# PL_DDR_Power.net
KiCad netlist of a schematic drawn in Altium Designer
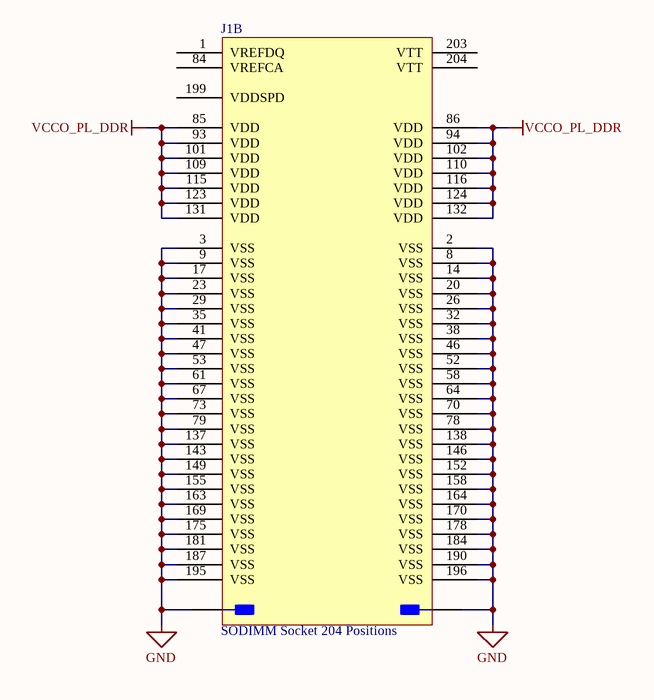
[diagram p0: PL_DDR_Power.SchDoc]

(export (version "E")
  (design (tool "Eeschema 10.0.6"))
  (components
    (comp (ref "J1")
      (value "SODIMM Socket 204 Positions")
      (footprint "TE_DDR3_SODIMM_RA_Socket")
      (description "Connector SODIMM Socket 204 Positions, Right Angle, DDR3/DDR3L +1.5V +1.35V")
      (libsource (lib "SpaceVNX") (part "2-2013310-1"))
    )
  )
  (nets
    (net (code "1") (name "GND") (class "Default")
      (node (ref "J1") (pin "137") (pinfunction "VSS_137") (pintype "passive"))
      (node (ref "J1") (pin "138") (pinfunction "VSS_138") (pintype "passive"))
      (node (ref "J1") (pin "14") (pinfunction "VSS_14") (pintype "passive"))
      (node (ref "J1") (pin "143") (pinfunction "VSS_143") (pintype "passive"))
      (node (ref "J1") (pin "146") (pinfunction "VSS_146") (pintype "passive"))
      (node (ref "J1") (pin "149") (pinfunction "VSS_149") (pintype "passive"))
      (node (ref "J1") (pin "152") (pinfunction "VSS_152") (pintype "passive"))
      (node (ref "J1") (pin "155") (pinfunction "VSS_155") (pintype "passive"))
      (node (ref "J1") (pin "158") (pinfunction "VSS_158") (pintype "passive"))
      (node (ref "J1") (pin "163") (pinfunction "VSS_163") (pintype "passive"))
      (node (ref "J1") (pin "164") (pinfunction "VSS_164") (pintype "passive"))
      (node (ref "J1") (pin "169") (pinfunction "VSS_169") (pintype "passive"))
      (node (ref "J1") (pin "17") (pinfunction "VSS_17") (pintype "passive"))
      (node (ref "J1") (pin "170") (pinfunction "VSS_170") (pintype "passive"))
      (node (ref "J1") (pin "175") (pinfunction "VSS_175") (pintype "passive"))
      (node (ref "J1") (pin "178") (pinfunction "VSS_178") (pintype "passive"))
      (node (ref "J1") (pin "181") (pinfunction "VSS_181") (pintype "passive"))
      (node (ref "J1") (pin "184") (pinfunction "VSS_184") (pintype "passive"))
      (node (ref "J1") (pin "187") (pinfunction "VSS_187") (pintype "passive"))
      (node (ref "J1") (pin "190") (pinfunction "VSS_190") (pintype "passive"))
      (node (ref "J1") (pin "195") (pinfunction "VSS_195") (pintype "passive"))
      (node (ref "J1") (pin "196") (pinfunction "VSS_196") (pintype "passive"))
      (node (ref "J1") (pin "2") (pinfunction "VSS_2") (pintype "passive"))
      (node (ref "J1") (pin "20") (pinfunction "VSS_20") (pintype "passive"))
      (node (ref "J1") (pin "205") (pinfunction "GND_205") (pintype "passive"))
      (node (ref "J1") (pin "206") (pinfunction "GND_206") (pintype "passive"))
      (node (ref "J1") (pin "23") (pinfunction "VSS_23") (pintype "passive"))
      (node (ref "J1") (pin "26") (pinfunction "VSS_26") (pintype "passive"))
      (node (ref "J1") (pin "29") (pinfunction "VSS_29") (pintype "passive"))
      (node (ref "J1") (pin "3") (pinfunction "VSS_3") (pintype "passive"))
      (node (ref "J1") (pin "32") (pinfunction "VSS_32") (pintype "passive"))
      (node (ref "J1") (pin "35") (pinfunction "VSS_35") (pintype "passive"))
      (node (ref "J1") (pin "38") (pinfunction "VSS_38") (pintype "passive"))
      (node (ref "J1") (pin "41") (pinfunction "VSS_41") (pintype "passive"))
      (node (ref "J1") (pin "46") (pinfunction "VSS_46") (pintype "passive"))
      (node (ref "J1") (pin "47") (pinfunction "VSS_47") (pintype "passive"))
      (node (ref "J1") (pin "52") (pinfunction "VSS_52") (pintype "passive"))
      (node (ref "J1") (pin "53") (pinfunction "VSS_53") (pintype "passive"))
      (node (ref "J1") (pin "58") (pinfunction "VSS_58") (pintype "passive"))
      (node (ref "J1") (pin "61") (pinfunction "VSS_61") (pintype "passive"))
      (node (ref "J1") (pin "64") (pinfunction "VSS_64") (pintype "passive"))
      (node (ref "J1") (pin "67") (pinfunction "VSS_67") (pintype "passive"))
      (node (ref "J1") (pin "70") (pinfunction "VSS_70") (pintype "passive"))
      (node (ref "J1") (pin "73") (pinfunction "VSS_73") (pintype "passive"))
      (node (ref "J1") (pin "78") (pinfunction "VSS_78") (pintype "passive"))
      (node (ref "J1") (pin "79") (pinfunction "VSS_79") (pintype "passive"))
      (node (ref "J1") (pin "8") (pinfunction "VSS_8") (pintype "passive"))
      (node (ref "J1") (pin "9") (pinfunction "VSS_9") (pintype "passive"))
    )
    (net (code "2") (name "VCCO_PL_DDR") (class "Default")
      (node (ref "J1") (pin "101") (pinfunction "VDD_101") (pintype "passive"))
      (node (ref "J1") (pin "102") (pinfunction "VDD_102") (pintype "passive"))
      (node (ref "J1") (pin "109") (pinfunction "VDD_109") (pintype "passive"))
      (node (ref "J1") (pin "110") (pinfunction "VDD_110") (pintype "passive"))
      (node (ref "J1") (pin "115") (pinfunction "VDD_115") (pintype "passive"))
      (node (ref "J1") (pin "116") (pinfunction "VDD_116") (pintype "passive"))
      (node (ref "J1") (pin "123") (pinfunction "VDD_123") (pintype "passive"))
      (node (ref "J1") (pin "124") (pinfunction "VDD_124") (pintype "passive"))
      (node (ref "J1") (pin "131") (pinfunction "VDD_131") (pintype "passive"))
      (node (ref "J1") (pin "132") (pinfunction "VDD_132") (pintype "passive"))
      (node (ref "J1") (pin "85") (pinfunction "VDD_85") (pintype "passive"))
      (node (ref "J1") (pin "86") (pinfunction "VDD_86") (pintype "passive"))
      (node (ref "J1") (pin "93") (pinfunction "VDD_93") (pintype "passive"))
      (node (ref "J1") (pin "94") (pinfunction "VDD_94") (pintype "passive"))
    )
    (net (code "3") (name "unconnected-(J1B-VDDSPD-Pad199)") (class "Default")
      (node (ref "J1") (pin "199") (pinfunction "VDDSPD_199") (pintype "passive"))
    )
    (net (code "4") (name "unconnected-(J1B-VREFCA-Pad84)") (class "Default")
      (node (ref "J1") (pin "84") (pinfunction "VREFCA_84") (pintype "passive"))
    )
    (net (code "5") (name "unconnected-(J1B-VREFDQ-Pad1)") (class "Default")
      (node (ref "J1") (pin "1") (pinfunction "VREFDQ_1") (pintype "passive"))
    )
    (net (code "6") (name "unconnected-(J1B-VTT-Pad203)") (class "Default")
      (node (ref "J1") (pin "203") (pinfunction "VTT_203") (pintype "passive"))
    )
    (net (code "7") (name "unconnected-(J1B-VTT-Pad204)") (class "Default")
      (node (ref "J1") (pin "204") (pinfunction "VTT_204") (pintype "passive"))
    )
  )
)
